# mic.net
KiCad netlist of a schematic drawn in Altium Designer
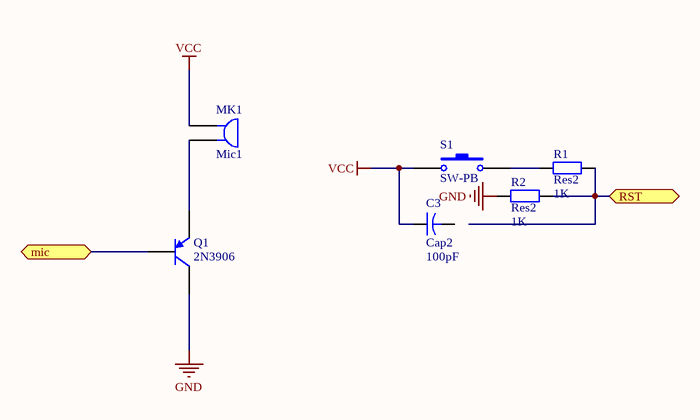
[diagram p0: mic.SchDoc]

(export (version "E")
  (design (tool "Eeschema 10.0.6"))
  (components
    (comp (ref "C3")
      (value "Cap2")
      (footprint "CAPR5-4X5")
      (description "Capacitor")
      (fields (field (name "ALTIUM_VALUE") "100pF") (field (name "PUBLISHER") "Altium Limited"))
      (libsource (lib "Miscellaneous Devices") (part "Cap2"))
    )
    (comp (ref "MK1")
      (value "Mic1")
      (footprint "PIN2")
      (description "Microphone")
      (fields (field (name "PUBLISHER") "Altium Limited"))
      (libsource (lib "Miscellaneous Devices") (part "Mic1"))
    )
    (comp (ref "Q1")
      (value "2N3906")
      (footprint "TO-92A")
      (description "PNP General Purpose Amplifier")
      (fields (field (name "PUBLISHER") "Altium Limited"))
      (libsource (lib "Miscellaneous Devices") (part "2N3906"))
    )
    (comp (ref "R1")
      (value "Res2")
      (footprint "AXIAL-0.4")
      (description "Resistor")
      (fields (field (name "ALTIUM_VALUE") "1K") (field (name "PUBLISHER") "Altium Limited"))
      (libsource (lib "Miscellaneous Devices") (part "Res2"))
    )
    (comp (ref "R2")
      (value "Res2")
      (footprint "AXIAL-0.4")
      (description "Resistor")
      (fields (field (name "ALTIUM_VALUE") "1K") (field (name "PUBLISHER") "Altium Limited"))
      (libsource (lib "Miscellaneous Devices") (part "Res2"))
    )
    (comp (ref "S1")
      (value "SW-PB")
      (footprint "SPST-2")
      (description "Switch")
      (fields (field (name "PUBLISHER") "Altium Limited"))
      (libsource (lib "Miscellaneous Devices") (part "SW-PB"))
    )
  )
  (nets
    (net (code "1") (name "/RST") (class "Default")
      (node (ref "R1") (pin "2") (pinfunction "2_2") (pintype "passive"))
      (node (ref "R2") (pin "2") (pinfunction "2_2") (pintype "passive"))
    )
    (net (code "2") (name "/mic") (class "Default")
      (node (ref "Q1") (pin "2") (pinfunction "B_2") (pintype "passive"))
    )
    (net (code "3") (name "GND") (class "Default")
      (node (ref "Q1") (pin "3") (pinfunction "C_3") (pintype "passive"))
      (node (ref "R2") (pin "1") (pinfunction "1_1") (pintype "passive"))
    )
    (net (code "4") (name "Net-(Q1-E)") (class "Default")
      (node (ref "MK1") (pin "2") (pinfunction "2_2") (pintype "passive"))
      (node (ref "Q1") (pin "1") (pinfunction "E_1") (pintype "passive"))
    )
    (net (code "5") (name "Net-(R1-Pad1)") (class "Default")
      (node (ref "R1") (pin "1") (pinfunction "1_1") (pintype "passive"))
      (node (ref "S1") (pin "2") (pinfunction "2_2") (pintype "passive"))
    )
    (net (code "6") (name "VCC") (class "Default")
      (node (ref "C3") (pin "1") (pinfunction "1_1") (pintype "passive"))
      (node (ref "MK1") (pin "1") (pinfunction "1_1") (pintype "passive"))
      (node (ref "S1") (pin "1") (pinfunction "1_1") (pintype "passive"))
    )
    (net (code "7") (name "unconnected-(C3-Pad2)") (class "Default")
      (node (ref "C3") (pin "2") (pinfunction "2_2") (pintype "passive"))
    )
  )
)
